# electro1.net
KiCad netlist of a schematic drawn in Altium Designer
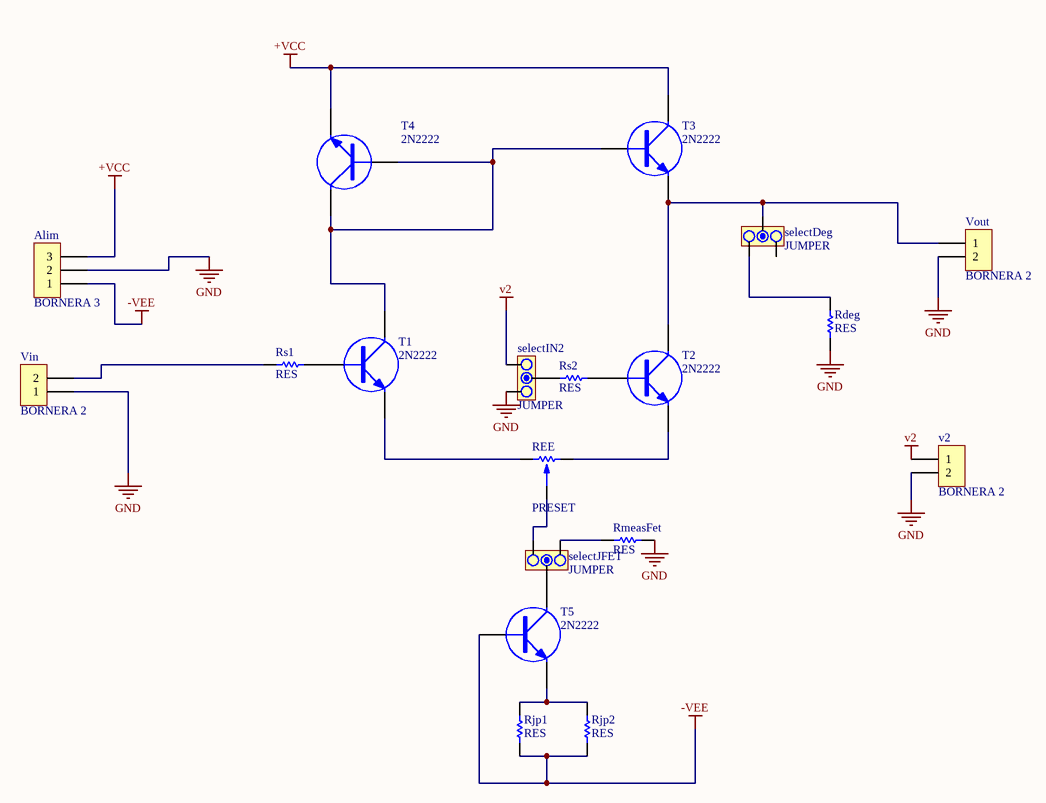
[diagram p0: electro1.SchDoc]

(export (version "E")
  (design (tool "Eeschema 10.0.6"))
  (components
    (comp (ref "Alim")
      (value "BORNERA 3")
      (footprint "BORNERA3")
      (libsource (lib "LIBEBAL") (part "BORNERA 3"))
    )
    (comp (ref "Rdeg") (value "RES") (footprint "RES300") (libsource (lib "LIBEBAL") (part "RES")))
    (comp (ref "REE") (value "PRESET") (footprint "PRESET V") (libsource (lib "LIBEBAL") (part "PRESET")))
    (comp (ref "Rjp1") (value "RES") (footprint "RES300") (libsource (lib "LIBEBAL") (part "RES")))
    (comp (ref "Rjp2") (value "RES") (footprint "RES300") (libsource (lib "LIBEBAL") (part "RES")))
    (comp (ref "RmeasFet") (value "RES") (footprint "RES300") (libsource (lib "LIBEBAL") (part "RES")))
    (comp (ref "Rs1") (value "RES") (footprint "RES300") (libsource (lib "LIBEBAL") (part "RES")))
    (comp (ref "Rs2") (value "RES") (footprint "RES300") (libsource (lib "LIBEBAL") (part "RES")))
    (comp (ref "selectDeg") (value "JUMPER") (footprint "JUMPER3") (libsource (lib "") (part "JUMPER3_2")))
    (comp (ref "selectIN2") (value "JUMPER") (footprint "JUMPER3") (libsource (lib "") (part "JUMPER3_1")))
    (comp (ref "selectJFET")
      (value "JUMPER")
      (footprint "JUMPER3")
      (libsource (lib "LIBEBAL") (part "JUMPER3"))
    )
    (comp (ref "T1") (value "2N2222") (footprint "TO92") (libsource (lib "LIBEBAL") (part "2N2222")))
    (comp (ref "T2") (value "2N2222") (footprint "TO92") (libsource (lib "LIBEBAL") (part "2N2222")))
    (comp (ref "T3") (value "2N2222") (footprint "TO92") (libsource (lib "LIBEBAL") (part "2N2222")))
    (comp (ref "T4") (value "2N2222") (footprint "TO92") (libsource (lib "LIBEBAL") (part "2N2222")))
    (comp (ref "T5") (value "2N2222") (footprint "TO92") (libsource (lib "LIBEBAL") (part "2N2222")))
    (comp (ref "v2")
      (value "BORNERA 2")
      (footprint "BORNERA2")
      (libsource (lib "LIBEBAL") (part "BORNERA 2"))
    )
    (comp (ref "Vin") (value "BORNERA 2") (footprint "BORNERA2") (libsource (lib "") (part "BORNERA 2_1")))
    (comp (ref "Vout")
      (value "BORNERA 2")
      (footprint "BORNERA2")
      (libsource (lib "LIBEBAL") (part "BORNERA 2"))
    )
  )
  (nets
    (net (code "1") (name "+VCC") (class "Default")
      (node (ref "Alim") (pin "3") (pinfunction "3_3") (pintype "passive"))
      (node (ref "T3") (pin "3") (pinfunction "C_3") (pintype "passive"))
      (node (ref "T4") (pin "2") (pinfunction "E_2") (pintype "passive"))
    )
    (net (code "2") (name "-VEE") (class "Default")
      (node (ref "Alim") (pin "1") (pinfunction "1_1") (pintype "passive"))
      (node (ref "Rjp1") (pin "1") (pinfunction "1_1") (pintype "passive"))
      (node (ref "Rjp2") (pin "1") (pinfunction "1_1") (pintype "passive"))
      (node (ref "T5") (pin "1") (pinfunction "B_1") (pintype "passive"))
    )
    (net (code "3") (name "GND") (class "Default")
      (node (ref "Alim") (pin "2") (pinfunction "2_2") (pintype "passive"))
      (node (ref "Rdeg") (pin "1") (pinfunction "1_1") (pintype "passive"))
      (node (ref "RmeasFet") (pin "2") (pinfunction "2_2") (pintype "passive"))
      (node (ref "Vin") (pin "1") (pinfunction "1_1") (pintype "passive"))
      (node (ref "Vout") (pin "2") (pinfunction "2_2") (pintype "passive"))
      (node (ref "selectIN2") (pin "1") (pinfunction "1_1") (pintype "passive"))
      (node (ref "v2") (pin "2") (pinfunction "2_2") (pintype "passive"))
    )
    (net (code "4") (name "Net-(REE-Pad2)") (class "Default")
      (node (ref "REE") (pin "2") (pinfunction "2_2") (pintype "passive"))
      (node (ref "selectJFET") (pin "1") (pinfunction "1_1") (pintype "passive"))
    )
    (net (code "5") (name "Net-(Rdeg-Pad2)") (class "Default")
      (node (ref "Rdeg") (pin "2") (pinfunction "2_2") (pintype "passive"))
      (node (ref "selectDeg") (pin "3") (pinfunction "3_3") (pintype "passive"))
    )
    (net (code "6") (name "Net-(RmeasFet-Pad1)") (class "Default")
      (node (ref "RmeasFet") (pin "1") (pinfunction "1_1") (pintype "passive"))
      (node (ref "selectJFET") (pin "3") (pinfunction "3_3") (pintype "passive"))
    )
    (net (code "7") (name "Net-(Rs1-Pad1)") (class "Default")
      (node (ref "Rs1") (pin "1") (pinfunction "1_1") (pintype "passive"))
      (node (ref "Vin") (pin "2") (pinfunction "2_2") (pintype "passive"))
    )
    (net (code "8") (name "Net-(Rs2-Pad1)") (class "Default")
      (node (ref "Rs2") (pin "1") (pinfunction "1_1") (pintype "passive"))
      (node (ref "selectIN2") (pin "2") (pinfunction "2_2") (pintype "passive"))
    )
    (net (code "9") (name "Net-(T1-B)") (class "Default")
      (node (ref "Rs1") (pin "2") (pinfunction "2_2") (pintype "passive"))
      (node (ref "T1") (pin "1") (pinfunction "B_1") (pintype "passive"))
    )
    (net (code "10") (name "Net-(T1-C)") (class "Default")
      (node (ref "T1") (pin "3") (pinfunction "C_3") (pintype "passive"))
      (node (ref "T3") (pin "1") (pinfunction "B_1") (pintype "passive"))
      (node (ref "T4") (pin "1") (pinfunction "B_1") (pintype "passive"))
      (node (ref "T4") (pin "3") (pinfunction "C_3") (pintype "passive"))
    )
    (net (code "11") (name "Net-(T1-E)") (class "Default")
      (node (ref "REE") (pin "3") (pinfunction "3_3") (pintype "passive"))
      (node (ref "T1") (pin "2") (pinfunction "E_2") (pintype "passive"))
    )
    (net (code "12") (name "Net-(T2-B)") (class "Default")
      (node (ref "Rs2") (pin "2") (pinfunction "2_2") (pintype "passive"))
      (node (ref "T2") (pin "1") (pinfunction "B_1") (pintype "passive"))
    )
    (net (code "13") (name "Net-(T2-C)") (class "Default")
      (node (ref "T2") (pin "3") (pinfunction "C_3") (pintype "passive"))
      (node (ref "T3") (pin "2") (pinfunction "E_2") (pintype "passive"))
      (node (ref "Vout") (pin "1") (pinfunction "1_1") (pintype "passive"))
      (node (ref "selectDeg") (pin "2") (pinfunction "2_2") (pintype "passive"))
    )
    (net (code "14") (name "Net-(T2-E)") (class "Default")
      (node (ref "REE") (pin "1") (pinfunction "1_1") (pintype "passive"))
      (node (ref "T2") (pin "2") (pinfunction "E_2") (pintype "passive"))
    )
    (net (code "15") (name "Net-(T5-C)") (class "Default")
      (node (ref "T5") (pin "3") (pinfunction "C_3") (pintype "passive"))
      (node (ref "selectJFET") (pin "2") (pinfunction "2_2") (pintype "passive"))
    )
    (net (code "16") (name "Net-(T5-E)") (class "Default")
      (node (ref "Rjp1") (pin "2") (pinfunction "2_2") (pintype "passive"))
      (node (ref "Rjp2") (pin "2") (pinfunction "2_2") (pintype "passive"))
      (node (ref "T5") (pin "2") (pinfunction "E_2") (pintype "passive"))
    )
    (net (code "17") (name "unconnected-(selectDeg-Pad1)") (class "Default")
      (node (ref "selectDeg") (pin "1") (pinfunction "1_1") (pintype "passive"))
    )
    (net (code "18") (name "v2") (class "Default")
      (node (ref "selectIN2") (pin "3") (pinfunction "3_3") (pintype "passive"))
      (node (ref "v2") (pin "1") (pinfunction "1_1") (pintype "passive"))
    )
  )
)
